# tempmonitor.net
KiCad netlist of a schematic drawn in EAGLE
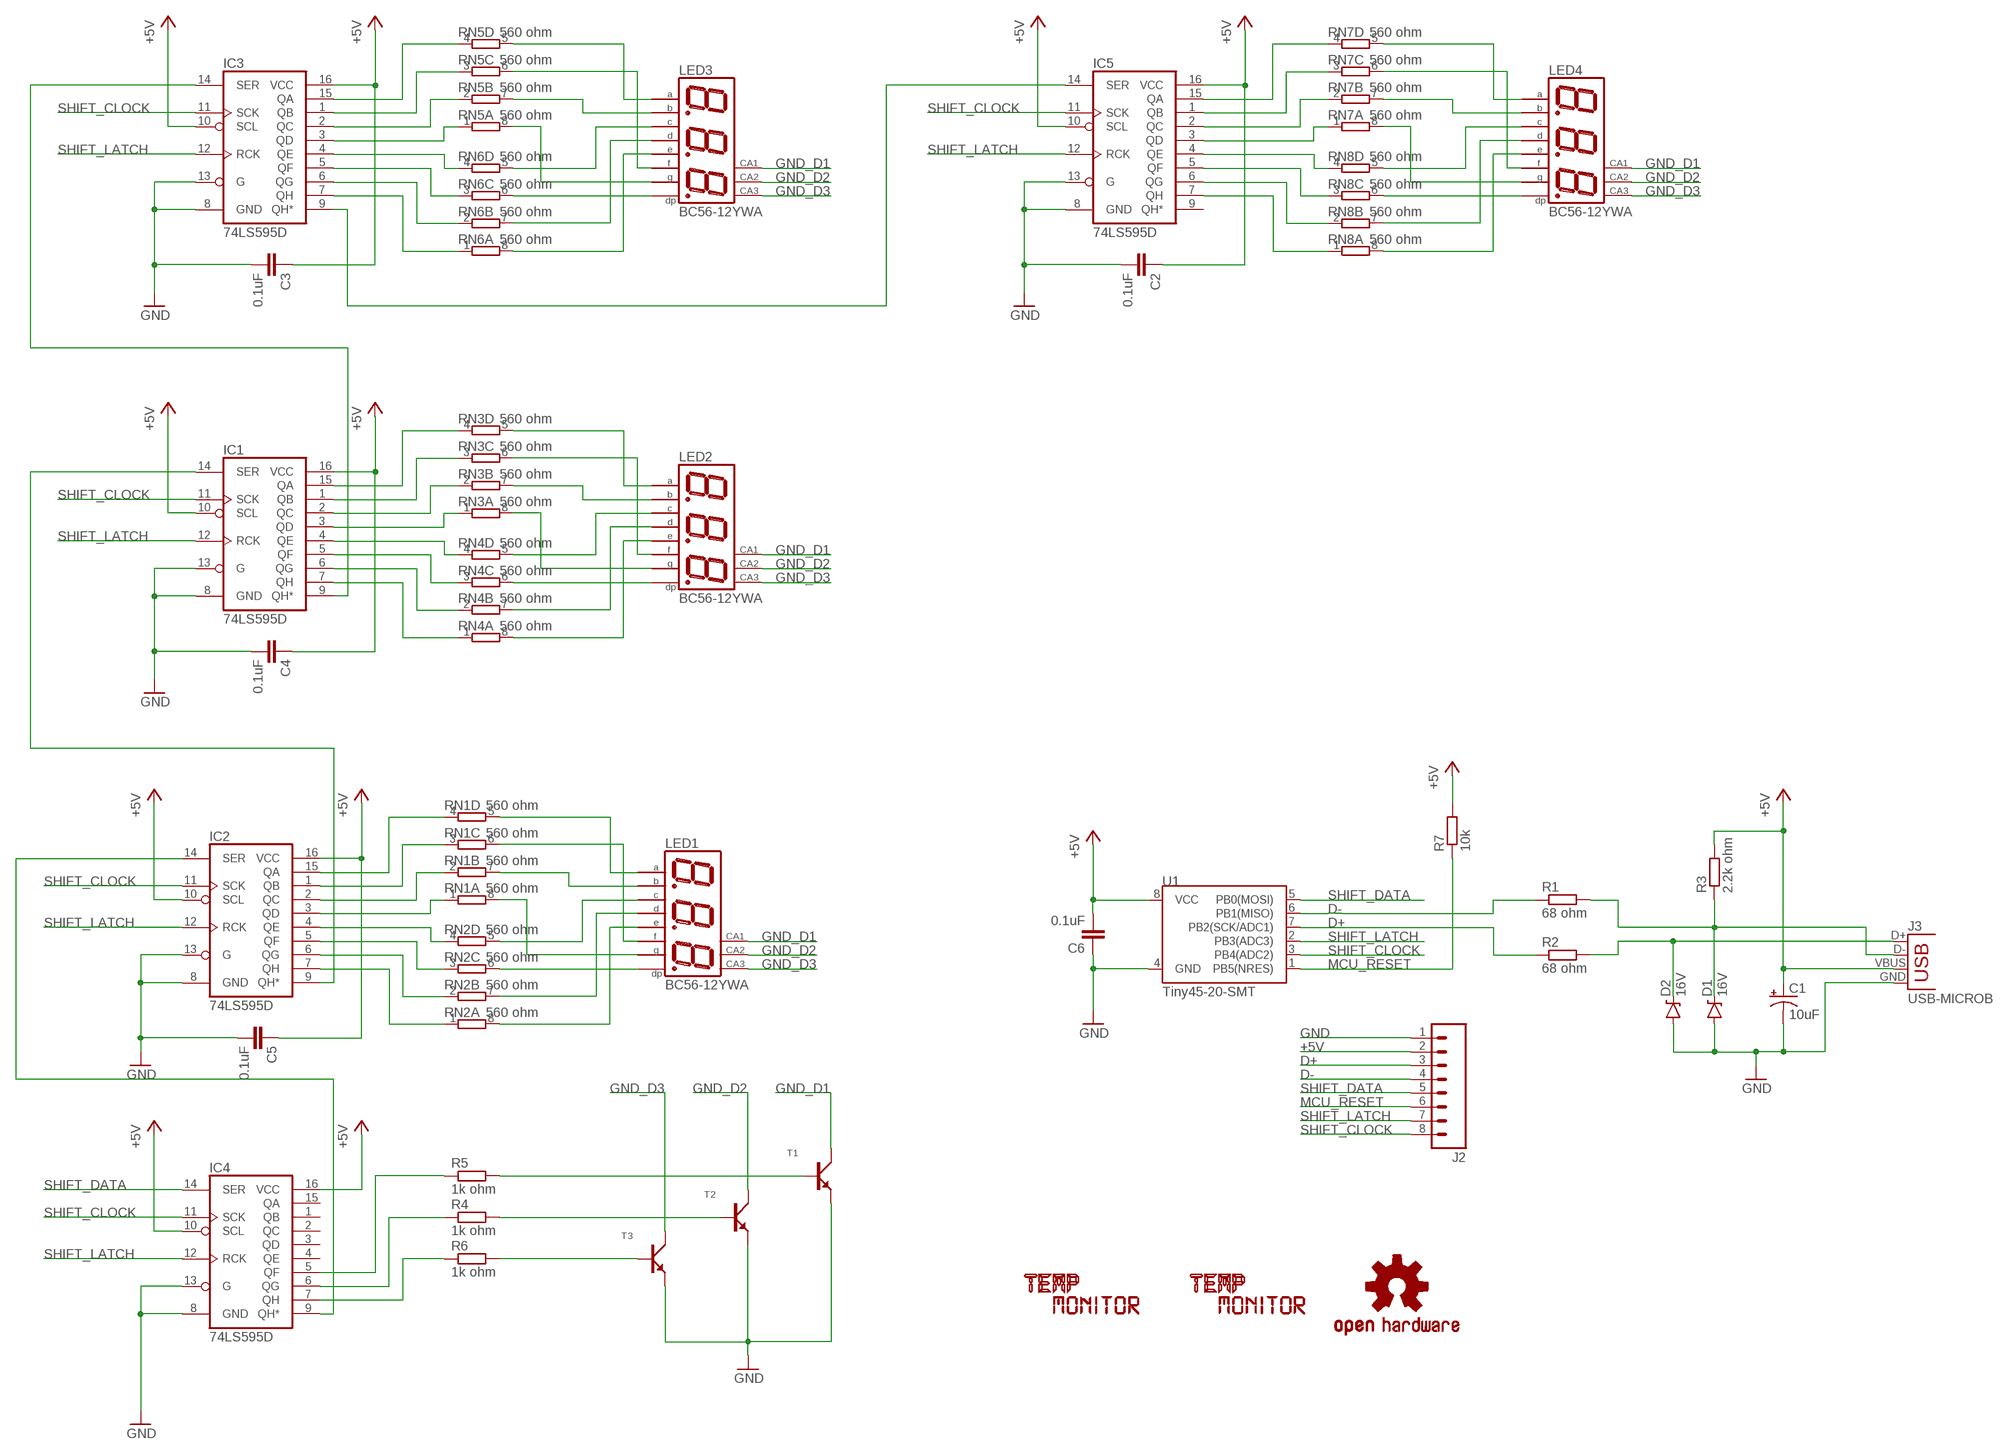
[diagram p0: schematic, sheet 1]

(export (version "E")
  (design (tool "Eeschema 10.0.6"))
  (components
    (comp (ref "C1")
      (value "10uF")
      (footprint "eagle-import:NIPPON_F80")
      (libsource (lib "eagle-import") (part "CAP_POLF80"))
    )
    (comp (ref "C2")
      (value "0.1uF")
      (footprint "eagle-import:C0805")
      (libsource (lib "eagle-import") (part "C-EUC0805"))
    )
    (comp (ref "C3")
      (value "0.1uF")
      (footprint "eagle-import:C0805")
      (libsource (lib "eagle-import") (part "C-EUC0805"))
    )
    (comp (ref "C4")
      (value "0.1uF")
      (footprint "eagle-import:C0805")
      (libsource (lib "eagle-import") (part "C-EUC0805"))
    )
    (comp (ref "C5")
      (value "0.1uF")
      (footprint "eagle-import:C0805")
      (libsource (lib "eagle-import") (part "C-EUC0805"))
    )
    (comp (ref "C6")
      (value "0.1uF")
      (footprint "eagle-import:C0805")
      (libsource (lib "eagle-import") (part "C-EUC0805"))
    )
    (comp (ref "D1")
      (value "16V")
      (footprint "eagle-import:SOD-123")
      (libsource (lib "eagle-import") (part "DIODE-ZENER16V"))
    )
    (comp (ref "D2")
      (value "16V")
      (footprint "eagle-import:SOD-123")
      (libsource (lib "eagle-import") (part "DIODE-ZENER16V"))
    )
    (comp (ref "IC1")
      (value "74LS595D")
      (footprint "eagle-import:SO16")
      (libsource (lib "eagle-import") (part "74595DLS"))
    )
    (comp (ref "IC2")
      (value "74LS595D")
      (footprint "eagle-import:SO16")
      (libsource (lib "eagle-import") (part "74595DLS"))
    )
    (comp (ref "IC3")
      (value "74LS595D")
      (footprint "eagle-import:SO16")
      (libsource (lib "eagle-import") (part "74595DLS"))
    )
    (comp (ref "IC4")
      (value "74LS595D")
      (footprint "eagle-import:SO16")
      (libsource (lib "eagle-import") (part "74595DLS"))
    )
    (comp (ref "IC5")
      (value "74LS595D")
      (footprint "eagle-import:SO16")
      (libsource (lib "eagle-import") (part "74595DLS"))
    )
    (comp (ref "J2")
      (value "TP_8")
      (footprint "eagle-import:TP_8")
      (libsource (lib "eagle-import") (part "TP_8"))
    )
    (comp (ref "J3")
      (value "USB-MICROB")
      (footprint "eagle-import:USB-MICROB")
      (libsource (lib "eagle-import") (part "USB-MICROB"))
    )
    (comp (ref "LED1")
      (value "BC56-12YWA")
      (footprint "eagle-import:BX56-12")
      (libsource (lib "eagle-import") (part "B?56-12WACY"))
    )
    (comp (ref "LED2")
      (value "BC56-12YWA")
      (footprint "eagle-import:BX56-12")
      (libsource (lib "eagle-import") (part "B?56-12WACY"))
    )
    (comp (ref "LED3")
      (value "BC56-12YWA")
      (footprint "eagle-import:BX56-12")
      (libsource (lib "eagle-import") (part "B?56-12WACY"))
    )
    (comp (ref "LED4")
      (value "BC56-12YWA")
      (footprint "eagle-import:BX56-12")
      (libsource (lib "eagle-import") (part "B?56-12WACY"))
    )
    (comp (ref "LOGO1")
      (value "OSHW-LOGOL")
      (footprint "eagle-import:OSHW-LOGO-L")
      (libsource (lib "eagle-import") (part "OSHW-LOGOL"))
    )
    (comp (ref "R1")
      (value "68 ohm")
      (footprint "eagle-import:R0805W")
      (libsource (lib "eagle-import") (part "R-EU_R0805W"))
    )
    (comp (ref "R2")
      (value "68 ohm")
      (footprint "eagle-import:R0805W")
      (libsource (lib "eagle-import") (part "R-EU_R0805W"))
    )
    (comp (ref "R3")
      (value "2.2k ohm")
      (footprint "eagle-import:R0805W")
      (libsource (lib "eagle-import") (part "R-EU_R0805W"))
    )
    (comp (ref "R4")
      (value "1k ohm")
      (footprint "eagle-import:R0805W")
      (libsource (lib "eagle-import") (part "R-EU_R0805W"))
    )
    (comp (ref "R5")
      (value "1k ohm")
      (footprint "eagle-import:R0805W")
      (libsource (lib "eagle-import") (part "R-EU_R0805W"))
    )
    (comp (ref "R6")
      (value "1k ohm")
      (footprint "eagle-import:R0805W")
      (libsource (lib "eagle-import") (part "R-EU_R0805W"))
    )
    (comp (ref "R7")
      (value "10k")
      (footprint "eagle-import:R0805W")
      (libsource (lib "eagle-import") (part "R-EU_R0805W"))
    )
    (comp (ref "RN1")
      (value "560 ohm")
      (footprint "eagle-import:EXBV8V")
      (libsource (lib "eagle-import") (part "4R-NEXBV8V"))
    )
    (comp (ref "RN2")
      (value "560 ohm")
      (footprint "eagle-import:EXBV8V")
      (libsource (lib "eagle-import") (part "4R-NEXBV8V"))
    )
    (comp (ref "RN3")
      (value "560 ohm")
      (footprint "eagle-import:EXBV8V")
      (libsource (lib "eagle-import") (part "4R-NEXBV8V"))
    )
    (comp (ref "RN4")
      (value "560 ohm")
      (footprint "eagle-import:EXBV8V")
      (libsource (lib "eagle-import") (part "4R-NEXBV8V"))
    )
    (comp (ref "RN5")
      (value "560 ohm")
      (footprint "eagle-import:EXBV8V")
      (libsource (lib "eagle-import") (part "4R-NEXBV8V"))
    )
    (comp (ref "RN6")
      (value "560 ohm")
      (footprint "eagle-import:EXBV8V")
      (libsource (lib "eagle-import") (part "4R-NEXBV8V"))
    )
    (comp (ref "RN7")
      (value "560 ohm")
      (footprint "eagle-import:EXBV8V")
      (libsource (lib "eagle-import") (part "4R-NEXBV8V"))
    )
    (comp (ref "RN8")
      (value "560 ohm")
      (footprint "eagle-import:EXBV8V")
      (libsource (lib "eagle-import") (part "4R-NEXBV8V"))
    )
    (comp (ref "T1")
      (value "NPN")
      (footprint "eagle-import:SOT23")
      (libsource (lib "eagle-import") (part "NPN"))
    )
    (comp (ref "T2")
      (value "NPN")
      (footprint "eagle-import:SOT23")
      (libsource (lib "eagle-import") (part "NPN"))
    )
    (comp (ref "T3")
      (value "NPN")
      (footprint "eagle-import:SOT23")
      (libsource (lib "eagle-import") (part "NPN"))
    )
    (comp (ref "U$1")
      (value "LOGO")
      (footprint "eagle-import:LOGO_M")
      (libsource (lib "eagle-import") (part "LOGO"))
    )
    (comp (ref "U$2")
      (value "LOGO")
      (footprint "eagle-import:LOGO_M")
      (libsource (lib "eagle-import") (part "LOGO"))
    )
    (comp (ref "U1")
      (value "Tiny45-20-SMT")
      (footprint "eagle-import:SO08-EIAJ")
      (libsource (lib "eagle-import") (part "ATTINY45TINY45-20-SMT"))
    )
  )
  (nets
    (net (code "1") (name "+5V") (class "Default")
      (node (ref "C1") (pin "+") (pinfunction "+_+") (pintype "passive"))
      (node (ref "C2") (pin "1") (pinfunction "1_1") (pintype "passive"))
      (node (ref "C3") (pin "1") (pinfunction "1_1") (pintype "passive"))
      (node (ref "C4") (pin "1") (pinfunction "1_1") (pintype "passive"))
      (node (ref "C5") (pin "1") (pinfunction "1_1") (pintype "passive"))
      (node (ref "C6") (pin "2") (pinfunction "2_2") (pintype "passive"))
      (node (ref "IC1") (pin "10") (pinfunction "SCL_10") (pintype "input"))
      (node (ref "IC1") (pin "16") (pinfunction "VCC_16") (pintype "power_in"))
      (node (ref "IC2") (pin "10") (pinfunction "SCL_10") (pintype "input"))
      (node (ref "IC2") (pin "16") (pinfunction "VCC_16") (pintype "power_in"))
      (node (ref "IC3") (pin "10") (pinfunction "SCL_10") (pintype "input"))
      (node (ref "IC3") (pin "16") (pinfunction "VCC_16") (pintype "power_in"))
      (node (ref "IC4") (pin "10") (pinfunction "SCL_10") (pintype "input"))
      (node (ref "IC4") (pin "16") (pinfunction "VCC_16") (pintype "power_in"))
      (node (ref "IC5") (pin "10") (pinfunction "SCL_10") (pintype "input"))
      (node (ref "IC5") (pin "16") (pinfunction "VCC_16") (pintype "power_in"))
      (node (ref "J2") (pin "2") (pinfunction "2_2") (pintype "passive"))
      (node (ref "J3") (pin "VBUS") (pinfunction "VBUS_VBUS") (pintype "bidirectional"))
      (node (ref "R3") (pin "2") (pinfunction "2_2") (pintype "passive"))
      (node (ref "R7") (pin "2") (pinfunction "2_2") (pintype "passive"))
      (node (ref "U1") (pin "8") (pinfunction "VCC_8") (pintype "bidirectional"))
    )
    (net (code "2") (name "/D+") (class "Default")
      (node (ref "J2") (pin "3") (pinfunction "3_3") (pintype "passive"))
      (node (ref "R2") (pin "1") (pinfunction "1_1") (pintype "passive"))
      (node (ref "U1") (pin "7") (pinfunction "PB2(SCK/ADC1)_7") (pintype "bidirectional"))
    )
    (net (code "3") (name "/D-") (class "Default")
      (node (ref "J2") (pin "4") (pinfunction "4_4") (pintype "passive"))
      (node (ref "R1") (pin "1") (pinfunction "1_1") (pintype "passive"))
      (node (ref "U1") (pin "6") (pinfunction "PB1(MISO)_6") (pintype "bidirectional"))
    )
    (net (code "4") (name "/GND_D1") (class "Default")
      (node (ref "LED1") (pin "12") (pinfunction "CA_12") (pintype "passive"))
      (node (ref "LED2") (pin "12") (pinfunction "CA_12") (pintype "passive"))
      (node (ref "LED3") (pin "12") (pinfunction "CA_12") (pintype "passive"))
      (node (ref "LED4") (pin "12") (pinfunction "CA_12") (pintype "passive"))
      (node (ref "T1") (pin "3") (pinfunction "C_3") (pintype "bidirectional"))
    )
    (net (code "5") (name "/GND_D2") (class "Default")
      (node (ref "LED1") (pin "9") (pinfunction "CA_9") (pintype "passive"))
      (node (ref "LED2") (pin "9") (pinfunction "CA_9") (pintype "passive"))
      (node (ref "LED3") (pin "9") (pinfunction "CA_9") (pintype "passive"))
      (node (ref "LED4") (pin "9") (pinfunction "CA_9") (pintype "passive"))
      (node (ref "T2") (pin "3") (pinfunction "C_3") (pintype "bidirectional"))
    )
    (net (code "6") (name "/GND_D3") (class "Default")
      (node (ref "LED1") (pin "8") (pinfunction "CA_8") (pintype "passive"))
      (node (ref "LED2") (pin "8") (pinfunction "CA_8") (pintype "passive"))
      (node (ref "LED3") (pin "8") (pinfunction "CA_8") (pintype "passive"))
      (node (ref "LED4") (pin "8") (pinfunction "CA_8") (pintype "passive"))
      (node (ref "T3") (pin "3") (pinfunction "C_3") (pintype "bidirectional"))
    )
    (net (code "7") (name "/MCU_RESET") (class "Default")
      (node (ref "J2") (pin "6") (pinfunction "6_6") (pintype "passive"))
      (node (ref "R7") (pin "1") (pinfunction "1_1") (pintype "passive"))
      (node (ref "U1") (pin "1") (pinfunction "PB5(NRES)_1") (pintype "bidirectional"))
    )
    (net (code "8") (name "/SHIFT_CLOCK") (class "Default")
      (node (ref "IC1") (pin "11") (pinfunction "SCK_11") (pintype "input"))
      (node (ref "IC2") (pin "11") (pinfunction "SCK_11") (pintype "input"))
      (node (ref "IC3") (pin "11") (pinfunction "SCK_11") (pintype "input"))
      (node (ref "IC4") (pin "11") (pinfunction "SCK_11") (pintype "input"))
      (node (ref "IC5") (pin "11") (pinfunction "SCK_11") (pintype "input"))
      (node (ref "J2") (pin "8") (pinfunction "8_8") (pintype "passive"))
      (node (ref "U1") (pin "3") (pinfunction "PB4(ADC2)_3") (pintype "bidirectional"))
    )
    (net (code "9") (name "/SHIFT_DATA") (class "Default")
      (node (ref "IC4") (pin "14") (pinfunction "SER_14") (pintype "input"))
      (node (ref "J2") (pin "5") (pinfunction "5_5") (pintype "passive"))
      (node (ref "U1") (pin "5") (pinfunction "PB0(MOSI)_5") (pintype "bidirectional"))
    )
    (net (code "10") (name "/SHIFT_LATCH") (class "Default")
      (node (ref "IC1") (pin "12") (pinfunction "RCK_12") (pintype "input"))
      (node (ref "IC2") (pin "12") (pinfunction "RCK_12") (pintype "input"))
      (node (ref "IC3") (pin "12") (pinfunction "RCK_12") (pintype "input"))
      (node (ref "IC4") (pin "12") (pinfunction "RCK_12") (pintype "input"))
      (node (ref "IC5") (pin "12") (pinfunction "RCK_12") (pintype "input"))
      (node (ref "J2") (pin "7") (pinfunction "7_7") (pintype "passive"))
      (node (ref "U1") (pin "2") (pinfunction "PB3(ADC3)_2") (pintype "bidirectional"))
    )
    (net (code "11") (name "GND") (class "Default")
      (node (ref "C1") (pin "-") (pinfunction "-_-") (pintype "passive"))
      (node (ref "C2") (pin "2") (pinfunction "2_2") (pintype "passive"))
      (node (ref "C3") (pin "2") (pinfunction "2_2") (pintype "passive"))
      (node (ref "C4") (pin "2") (pinfunction "2_2") (pintype "passive"))
      (node (ref "C5") (pin "2") (pinfunction "2_2") (pintype "passive"))
      (node (ref "C6") (pin "1") (pinfunction "1_1") (pintype "passive"))
      (node (ref "D1") (pin "A") (pinfunction "A_A") (pintype "passive"))
      (node (ref "D2") (pin "A") (pinfunction "A_A") (pintype "passive"))
      (node (ref "IC1") (pin "13") (pinfunction "G_13") (pintype "input"))
      (node (ref "IC1") (pin "8") (pinfunction "GND_8") (pintype "power_in"))
      (node (ref "IC2") (pin "13") (pinfunction "G_13") (pintype "input"))
      (node (ref "IC2") (pin "8") (pinfunction "GND_8") (pintype "power_in"))
      (node (ref "IC3") (pin "13") (pinfunction "G_13") (pintype "input"))
      (node (ref "IC3") (pin "8") (pinfunction "GND_8") (pintype "power_in"))
      (node (ref "IC4") (pin "13") (pinfunction "G_13") (pintype "input"))
      (node (ref "IC4") (pin "8") (pinfunction "GND_8") (pintype "power_in"))
      (node (ref "IC5") (pin "13") (pinfunction "G_13") (pintype "input"))
      (node (ref "IC5") (pin "8") (pinfunction "GND_8") (pintype "power_in"))
      (node (ref "J2") (pin "1") (pinfunction "1_1") (pintype "passive"))
      (node (ref "J3") (pin "GND") (pinfunction "GND_GND") (pintype "bidirectional"))
      (node (ref "T1") (pin "2") (pinfunction "E_2") (pintype "bidirectional"))
      (node (ref "T2") (pin "2") (pinfunction "E_2") (pintype "bidirectional"))
      (node (ref "T3") (pin "2") (pinfunction "E_2") (pintype "bidirectional"))
      (node (ref "U1") (pin "4") (pinfunction "GND_4") (pintype "bidirectional"))
    )
    (net (code "12") (name "Net-(D1-PadC)") (class "Default")
      (node (ref "D1") (pin "C") (pinfunction "C_C") (pintype "passive"))
      (node (ref "J3") (pin "D-") (pinfunction "D-_D-") (pintype "bidirectional"))
      (node (ref "R1") (pin "2") (pinfunction "2_2") (pintype "passive"))
      (node (ref "R3") (pin "1") (pinfunction "1_1") (pintype "passive"))
    )
    (net (code "13") (name "Net-(D2-PadC)") (class "Default")
      (node (ref "D2") (pin "C") (pinfunction "C_C") (pintype "passive"))
      (node (ref "J3") (pin "D+") (pinfunction "D+_D+") (pintype "bidirectional"))
      (node (ref "R2") (pin "2") (pinfunction "2_2") (pintype "passive"))
    )
    (net (code "14") (name "Net-(IC1-QA)") (class "Default")
      (node (ref "IC1") (pin "15") (pinfunction "QA_15") (pintype "tri_state"))
      (node (ref "RN3") (pin "4") (pinfunction "1_4") (pintype "passive"))
    )
    (net (code "15") (name "Net-(IC1-QB)") (class "Default")
      (node (ref "IC1") (pin "1") (pinfunction "QB_1") (pintype "tri_state"))
      (node (ref "RN3") (pin "3") (pinfunction "1_3") (pintype "passive"))
    )
    (net (code "16") (name "Net-(IC1-QC)") (class "Default")
      (node (ref "IC1") (pin "2") (pinfunction "QC_2") (pintype "tri_state"))
      (node (ref "RN3") (pin "2") (pinfunction "1_2") (pintype "passive"))
    )
    (net (code "17") (name "Net-(IC1-QD)") (class "Default")
      (node (ref "IC1") (pin "3") (pinfunction "QD_3") (pintype "tri_state"))
      (node (ref "RN3") (pin "1") (pinfunction "1_1") (pintype "passive"))
    )
    (net (code "18") (name "Net-(IC1-QE)") (class "Default")
      (node (ref "IC1") (pin "4") (pinfunction "QE_4") (pintype "tri_state"))
      (node (ref "RN4") (pin "4") (pinfunction "1_4") (pintype "passive"))
    )
    (net (code "19") (name "Net-(IC1-QF)") (class "Default")
      (node (ref "IC1") (pin "5") (pinfunction "QF_5") (pintype "tri_state"))
      (node (ref "RN4") (pin "3") (pinfunction "1_3") (pintype "passive"))
    )
    (net (code "20") (name "Net-(IC1-QG)") (class "Default")
      (node (ref "IC1") (pin "6") (pinfunction "QG_6") (pintype "tri_state"))
      (node (ref "RN4") (pin "2") (pinfunction "1_2") (pintype "passive"))
    )
    (net (code "21") (name "Net-(IC1-QH)") (class "Default")
      (node (ref "IC1") (pin "7") (pinfunction "QH_7") (pintype "tri_state"))
      (node (ref "RN4") (pin "1") (pinfunction "1_1") (pintype "passive"))
    )
    (net (code "22") (name "Net-(IC1-QH*)") (class "Default")
      (node (ref "IC1") (pin "9") (pinfunction "QH*_9") (pintype "tri_state"))
      (node (ref "IC3") (pin "14") (pinfunction "SER_14") (pintype "input"))
    )
    (net (code "23") (name "Net-(IC1-SER)") (class "Default")
      (node (ref "IC1") (pin "14") (pinfunction "SER_14") (pintype "input"))
      (node (ref "IC2") (pin "9") (pinfunction "QH*_9") (pintype "tri_state"))
    )
    (net (code "24") (name "Net-(IC2-QA)") (class "Default")
      (node (ref "IC2") (pin "15") (pinfunction "QA_15") (pintype "tri_state"))
      (node (ref "RN1") (pin "4") (pinfunction "1_4") (pintype "passive"))
    )
    (net (code "25") (name "Net-(IC2-QB)") (class "Default")
      (node (ref "IC2") (pin "1") (pinfunction "QB_1") (pintype "tri_state"))
      (node (ref "RN1") (pin "3") (pinfunction "1_3") (pintype "passive"))
    )
    (net (code "26") (name "Net-(IC2-QC)") (class "Default")
      (node (ref "IC2") (pin "2") (pinfunction "QC_2") (pintype "tri_state"))
      (node (ref "RN1") (pin "2") (pinfunction "1_2") (pintype "passive"))
    )
    (net (code "27") (name "Net-(IC2-QD)") (class "Default")
      (node (ref "IC2") (pin "3") (pinfunction "QD_3") (pintype "tri_state"))
      (node (ref "RN1") (pin "1") (pinfunction "1_1") (pintype "passive"))
    )
    (net (code "28") (name "Net-(IC2-QE)") (class "Default")
      (node (ref "IC2") (pin "4") (pinfunction "QE_4") (pintype "tri_state"))
      (node (ref "RN2") (pin "4") (pinfunction "1_4") (pintype "passive"))
    )
    (net (code "29") (name "Net-(IC2-QF)") (class "Default")
      (node (ref "IC2") (pin "5") (pinfunction "QF_5") (pintype "tri_state"))
      (node (ref "RN2") (pin "3") (pinfunction "1_3") (pintype "passive"))
    )
    (net (code "30") (name "Net-(IC2-QG)") (class "Default")
      (node (ref "IC2") (pin "6") (pinfunction "QG_6") (pintype "tri_state"))
      (node (ref "RN2") (pin "2") (pinfunction "1_2") (pintype "passive"))
    )
    (net (code "31") (name "Net-(IC2-QH)") (class "Default")
      (node (ref "IC2") (pin "7") (pinfunction "QH_7") (pintype "tri_state"))
      (node (ref "RN2") (pin "1") (pinfunction "1_1") (pintype "passive"))
    )
    (net (code "32") (name "Net-(IC2-SER)") (class "Default")
      (node (ref "IC2") (pin "14") (pinfunction "SER_14") (pintype "input"))
      (node (ref "IC4") (pin "9") (pinfunction "QH*_9") (pintype "tri_state"))
    )
    (net (code "33") (name "Net-(IC3-QA)") (class "Default")
      (node (ref "IC3") (pin "15") (pinfunction "QA_15") (pintype "tri_state"))
      (node (ref "RN5") (pin "4") (pinfunction "1_4") (pintype "passive"))
    )
    (net (code "34") (name "Net-(IC3-QB)") (class "Default")
      (node (ref "IC3") (pin "1") (pinfunction "QB_1") (pintype "tri_state"))
      (node (ref "RN5") (pin "3") (pinfunction "1_3") (pintype "passive"))
    )
    (net (code "35") (name "Net-(IC3-QC)") (class "Default")
      (node (ref "IC3") (pin "2") (pinfunction "QC_2") (pintype "tri_state"))
      (node (ref "RN5") (pin "2") (pinfunction "1_2") (pintype "passive"))
    )
    (net (code "36") (name "Net-(IC3-QD)") (class "Default")
      (node (ref "IC3") (pin "3") (pinfunction "QD_3") (pintype "tri_state"))
      (node (ref "RN5") (pin "1") (pinfunction "1_1") (pintype "passive"))
    )
    (net (code "37") (name "Net-(IC3-QE)") (class "Default")
      (node (ref "IC3") (pin "4") (pinfunction "QE_4") (pintype "tri_state"))
      (node (ref "RN6") (pin "4") (pinfunction "1_4") (pintype "passive"))
    )
    (net (code "38") (name "Net-(IC3-QF)") (class "Default")
      (node (ref "IC3") (pin "5") (pinfunction "QF_5") (pintype "tri_state"))
      (node (ref "RN6") (pin "3") (pinfunction "1_3") (pintype "passive"))
    )
    (net (code "39") (name "Net-(IC3-QG)") (class "Default")
      (node (ref "IC3") (pin "6") (pinfunction "QG_6") (pintype "tri_state"))
      (node (ref "RN6") (pin "2") (pinfunction "1_2") (pintype "passive"))
    )
    (net (code "40") (name "Net-(IC3-QH)") (class "Default")
      (node (ref "IC3") (pin "7") (pinfunction "QH_7") (pintype "tri_state"))
      (node (ref "RN6") (pin "1") (pinfunction "1_1") (pintype "passive"))
    )
    (net (code "41") (name "Net-(IC3-QH*)") (class "Default")
      (node (ref "IC3") (pin "9") (pinfunction "QH*_9") (pintype "tri_state"))
      (node (ref "IC5") (pin "14") (pinfunction "SER_14") (pintype "input"))
    )
    (net (code "42") (name "Net-(IC4-QF)") (class "Default")
      (node (ref "IC4") (pin "5") (pinfunction "QF_5") (pintype "tri_state"))
      (node (ref "R5") (pin "1") (pinfunction "1_1") (pintype "passive"))
    )
    (net (code "43") (name "Net-(IC4-QG)") (class "Default")
      (node (ref "IC4") (pin "6") (pinfunction "QG_6") (pintype "tri_state"))
      (node (ref "R4") (pin "1") (pinfunction "1_1") (pintype "passive"))
    )
    (net (code "44") (name "Net-(IC4-QH)") (class "Default")
      (node (ref "IC4") (pin "7") (pinfunction "QH_7") (pintype "tri_state"))
      (node (ref "R6") (pin "1") (pinfunction "1_1") (pintype "passive"))
    )
    (net (code "45") (name "Net-(IC5-QA)") (class "Default")
      (node (ref "IC5") (pin "15") (pinfunction "QA_15") (pintype "tri_state"))
      (node (ref "RN7") (pin "4") (pinfunction "1_4") (pintype "passive"))
    )
    (net (code "46") (name "Net-(IC5-QB)") (class "Default")
      (node (ref "IC5") (pin "1") (pinfunction "QB_1") (pintype "tri_state"))
      (node (ref "RN7") (pin "3") (pinfunction "1_3") (pintype "passive"))
    )
    (net (code "47") (name "Net-(IC5-QC)") (class "Default")
      (node (ref "IC5") (pin "2") (pinfunction "QC_2") (pintype "tri_state"))
      (node (ref "RN7") (pin "2") (pinfunction "1_2") (pintype "passive"))
    )
    (net (code "48") (name "Net-(IC5-QD)") (class "Default")
      (node (ref "IC5") (pin "3") (pinfunction "QD_3") (pintype "tri_state"))
      (node (ref "RN7") (pin "1") (pinfunction "1_1") (pintype "passive"))
    )
    (net (code "49") (name "Net-(IC5-QE)") (class "Default")
      (node (ref "IC5") (pin "4") (pinfunction "QE_4") (pintype "tri_state"))
      (node (ref "RN8") (pin "4") (pinfunction "1_4") (pintype "passive"))
    )
    (net (code "50") (name "Net-(IC5-QF)") (class "Default")
      (node (ref "IC5") (pin "5") (pinfunction "QF_5") (pintype "tri_state"))
      (node (ref "RN8") (pin "3") (pinfunction "1_3") (pintype "passive"))
    )
    (net (code "51") (name "Net-(IC5-QG)") (class "Default")
      (node (ref "IC5") (pin "6") (pinfunction "QG_6") (pintype "tri_state"))
      (node (ref "RN8") (pin "2") (pinfunction "1_2") (pintype "passive"))
    )
    (net (code "52") (name "Net-(IC5-QH)") (class "Default")
      (node (ref "IC5") (pin "7") (pinfunction "QH_7") (pintype "tri_state"))
      (node (ref "RN8") (pin "1") (pinfunction "1_1") (pintype "passive"))
    )
    (net (code "53") (name "Net-(LED1-A)") (class "Default")
      (node (ref "LED1") (pin "11") (pinfunction "A_11") (pintype "passive"))
      (node (ref "RN1") (pin "5") (pinfunction "2_5") (pintype "passive"))
    )
    (net (code "54") (name "Net-(LED1-B)") (class "Default")
      (node (ref "LED1") (pin "7") (pinfunction "B_7") (pintype "passive"))
      (node (ref "RN1") (pin "7") (pinfunction "2_7") (pintype "passive"))
    )
    (net (code "55") (name "Net-(LED1-C)") (class "Default")
      (node (ref "LED1") (pin "4") (pinfunction "C_4") (pintype "passive"))
      (node (ref "RN2") (pin "5") (pinfunction "2_5") (pintype "passive"))
    )
    (net (code "56") (name "Net-(LED1-D)") (class "Default")
      (node (ref "LED1") (pin "2") (pinfunction "D_2") (pintype "passive"))
      (node (ref "RN2") (pin "7") (pinfunction "2_7") (pintype "passive"))
    )
    (net (code "57") (name "Net-(LED1-DP)") (class "Default")
      (node (ref "LED1") (pin "3") (pinfunction "DP_3") (pintype "passive"))
      (node (ref "RN2") (pin "6") (pinfunction "2_6") (pintype "passive"))
    )
    (net (code "58") (name "Net-(LED1-E)") (class "Default")
      (node (ref "LED1") (pin "1") (pinfunction "E_1") (pintype "passive"))
      (node (ref "RN2") (pin "8") (pinfunction "2_8") (pintype "passive"))
    )
    (net (code "59") (name "Net-(LED1-F)") (class "Default")
      (node (ref "LED1") (pin "10") (pinfunction "F_10") (pintype "passive"))
      (node (ref "RN1") (pin "6") (pinfunction "2_6") (pintype "passive"))
    )
    (net (code "60") (name "Net-(LED1-G)") (class "Default")
      (node (ref "LED1") (pin "5") (pinfunction "G_5") (pintype "passive"))
      (node (ref "RN1") (pin "8") (pinfunction "2_8") (pintype "passive"))
    )
    (net (code "61") (name "Net-(LED2-A)") (class "Default")
      (node (ref "LED2") (pin "11") (pinfunction "A_11") (pintype "passive"))
      (node (ref "RN3") (pin "5") (pinfunction "2_5") (pintype "passive"))
    )
    (net (code "62") (name "Net-(LED2-B)") (class "Default")
      (node (ref "LED2") (pin "7") (pinfunction "B_7") (pintype "passive"))
      (node (ref "RN3") (pin "7") (pinfunction "2_7") (pintype "passive"))
    )
    (net (code "63") (name "Net-(LED2-C)") (class "Default")
      (node (ref "LED2") (pin "4") (pinfunction "C_4") (pintype "passive"))
      (node (ref "RN4") (pin "5") (pinfunction "2_5") (pintype "passive"))
    )
    (net (code "64") (name "Net-(LED2-D)") (class "Default")
      (node (ref "LED2") (pin "2") (pinfunction "D_2") (pintype "passive"))
      (node (ref "RN4") (pin "7") (pinfunction "2_7") (pintype "passive"))
    )
    (net (code "65") (name "Net-(LED2-DP)") (class "Default")
      (node (ref "LED2") (pin "3") (pinfunction "DP_3") (pintype "passive"))
      (node (ref "RN4") (pin "6") (pinfunction "2_6") (pintype "passive"))
    )
    (net (code "66") (name "Net-(LED2-E)") (class "Default")
      (node (ref "LED2") (pin "1") (pinfunction "E_1") (pintype "passive"))
      (node (ref "RN4") (pin "8") (pinfunction "2_8") (pintype "passive"))
    )
    (net (code "67") (name "Net-(LED2-F)") (class "Default")
      (node (ref "LED2") (pin "10") (pinfunction "F_10") (pintype "passive"))
      (node (ref "RN3") (pin "6") (pinfunction "2_6") (pintype "passive"))
    )
    (net (code "68") (name "Net-(LED2-G)") (class "Default")
      (node (ref "LED2") (pin "5") (pinfunction "G_5") (pintype "passive"))
      (node (ref "RN3") (pin "8") (pinfunction "2_8") (pintype "passive"))
    )
    (net (code "69") (name "Net-(LED3-A)") (class "Default")
      (node (ref "LED3") (pin "11") (pinfunction "A_11") (pintype "passive"))
      (node (ref "RN5") (pin "5") (pinfunction "2_5") (pintype "passive"))
    )
    (net (code "70") (name "Net-(LED3-B)") (class "Default")
      (node (ref "LED3") (pin "7") (pinfunction "B_7") (pintype "passive"))
      (node (ref "RN5") (pin "7") (pinfunction "2_7") (pintype "passive"))
    )
    (net (code "71") (name "Net-(LED3-C)") (class "Default")
      (node (ref "LED3") (pin "4") (pinfunction "C_4") (pintype "passive"))
      (node (ref "RN6") (pin "5") (pinfunction "2_5") (pintype "passive"))
    )
    (net (code "72") (name "Net-(LED3-D)") (class "Default")
      (node (ref "LED3") (pin "2") (pinfunction "D_2") (pintype "passive"))
      (node (ref "RN6") (pin "7") (pinfunction "2_7") (pintype "passive"))
    )
    (net (code "73") (name "Net-(LED3-DP)") (class "Default")
      (node (ref "LED3") (pin "3") (pinfunction "DP_3") (pintype "passive"))
      (node (ref "RN6") (pin "6") (pinfunction "2_6") (pintype "passive"))
    )
    (net (code "74") (name "Net-(LED3-E)") (class "Default")
      (node (ref "LED3") (pin "1") (pinfunction "E_1") (pintype "passive"))
      (node (ref "RN6") (pin "8") (pinfunction "2_8") (pintype "passive"))
    )
    (net (code "75") (name "Net-(LED3-F)") (class "Default")
      (node (ref "LED3") (pin "10") (pinfunction "F_10") (pintype "passive"))
      (node (ref "RN5") (pin "6") (pinfunction "2_6") (pintype "passive"))
    )
    (net (code "76") (name "Net-(LED3-G)") (class "Default")
      (node (ref "LED3") (pin "5") (pinfunction "G_5") (pintype "passive"))
      (node (ref "RN5") (pin "8") (pinfunction "2_8") (pintype "passive"))
    )
    (net (code "77") (name "Net-(LED4-A)") (class "Default")
      (node (ref "LED4") (pin "11") (pinfunction "A_11") (pintype "passive"))
      (node (ref "RN7") (pin "5") (pinfunction "2_5") (pintype "passive"))
    )
    (net (code "78") (name "Net-(LED4-B)") (class "Default")
      (node (ref "LED4") (pin "7") (pinfunction "B_7") (pintype "passive"))
      (node (ref "RN7") (pin "7") (pinfunction "2_7") (pintype "passive"))
    )
    (net (code "79") (name "Net-(LED4-C)") (class "Default")
      (node (ref "LED4") (pin "4") (pinfunction "C_4") (pintype "passive"))
      (node (ref "RN8") (pin "5") (pinfunction "2_5") (pintype "passive"))
    )
    (net (code "80") (name "Net-(LED4-D)") (class "Default")
      (node (ref "LED4") (pin "2") (pinfunction "D_2") (pintype "passive"))
      (node (ref "RN8") (pin "7") (pinfunction "2_7") (pintype "passive"))
    )
    (net (code "81") (name "Net-(LED4-DP)") (class "Default")
      (node (ref "LED4") (pin "3") (pinfunction "DP_3") (pintype "passive"))
      (node (ref "RN8") (pin "6") (pinfunction "2_6") (pintype "passive"))
    )
    (net (code "82") (name "Net-(LED4-E)") (class "Default")
      (node (ref "LED4") (pin "1") (pinfunction "E_1") (pintype "passive"))
      (node (ref "RN8") (pin "8") (pinfunction "2_8") (pintype "passive"))
    )
    (net (code "83") (name "Net-(LED4-F)") (class "Default")
      (node (ref "LED4") (pin "10") (pinfunction "F_10") (pintype "passive"))
      (node (ref "RN7") (pin "6") (pinfunction "2_6") (pintype "passive"))
    )
    (net (code "84") (name "Net-(LED4-G)") (class "Default")
      (node (ref "LED4") (pin "5") (pinfunction "G_5") (pintype "passive"))
      (node (ref "RN7") (pin "8") (pinfunction "2_8") (pintype "passive"))
    )
    (net (code "85") (name "Net-(T1-B)") (class "Default")
      (node (ref "R5") (pin "2") (pinfunction "2_2") (pintype "passive"))
      (node (ref "T1") (pin "1") (pinfunction "B_1") (pintype "bidirectional"))
    )
    (net (code "86") (name "Net-(T2-B)") (class "Default")
      (node (ref "R4") (pin "2") (pinfunction "2_2") (pintype "passive"))
      (node (ref "T2") (pin "1") (pinfunction "B_1") (pintype "bidirectional"))
    )
    (net (code "87") (name "Net-(T3-B)") (class "Default")
      (node (ref "R6") (pin "2") (pinfunction "2_2") (pintype "passive"))
      (node (ref "T3") (pin "1") (pinfunction "B_1") (pintype "bidirectional"))
    )
    (net (code "88") (name "unconnected-(IC4-QA-Pad15)") (class "Default")
      (node (ref "IC4") (pin "15") (pinfunction "QA_15") (pintype "tri_state"))
    )
    (net (code "89") (name "unconnected-(IC4-QB-Pad1)") (class "Default")
      (node (ref "IC4") (pin "1") (pinfunction "QB_1") (pintype "tri_state"))
    )
    (net (code "90") (name "unconnected-(IC4-QC-Pad2)") (class "Default")
      (node (ref "IC4") (pin "2") (pinfunction "QC_2") (pintype "tri_state"))
    )
    (net (code "91") (name "unconnected-(IC4-QD-Pad3)") (class "Default")
      (node (ref "IC4") (pin "3") (pinfunction "QD_3") (pintype "tri_state"))
    )
    (net (code "92") (name "unconnected-(IC4-QE-Pad4)") (class "Default")
      (node (ref "IC4") (pin "4") (pinfunction "QE_4") (pintype "tri_state"))
    )
    (net (code "93") (name "unconnected-(IC5-QH*-Pad9)") (class "Default")
      (node (ref "IC5") (pin "9") (pinfunction "QH*_9") (pintype "tri_state"))
    )
  )
)
